# RadioSheet.net
KiCad netlist of a schematic drawn in Altium Designer
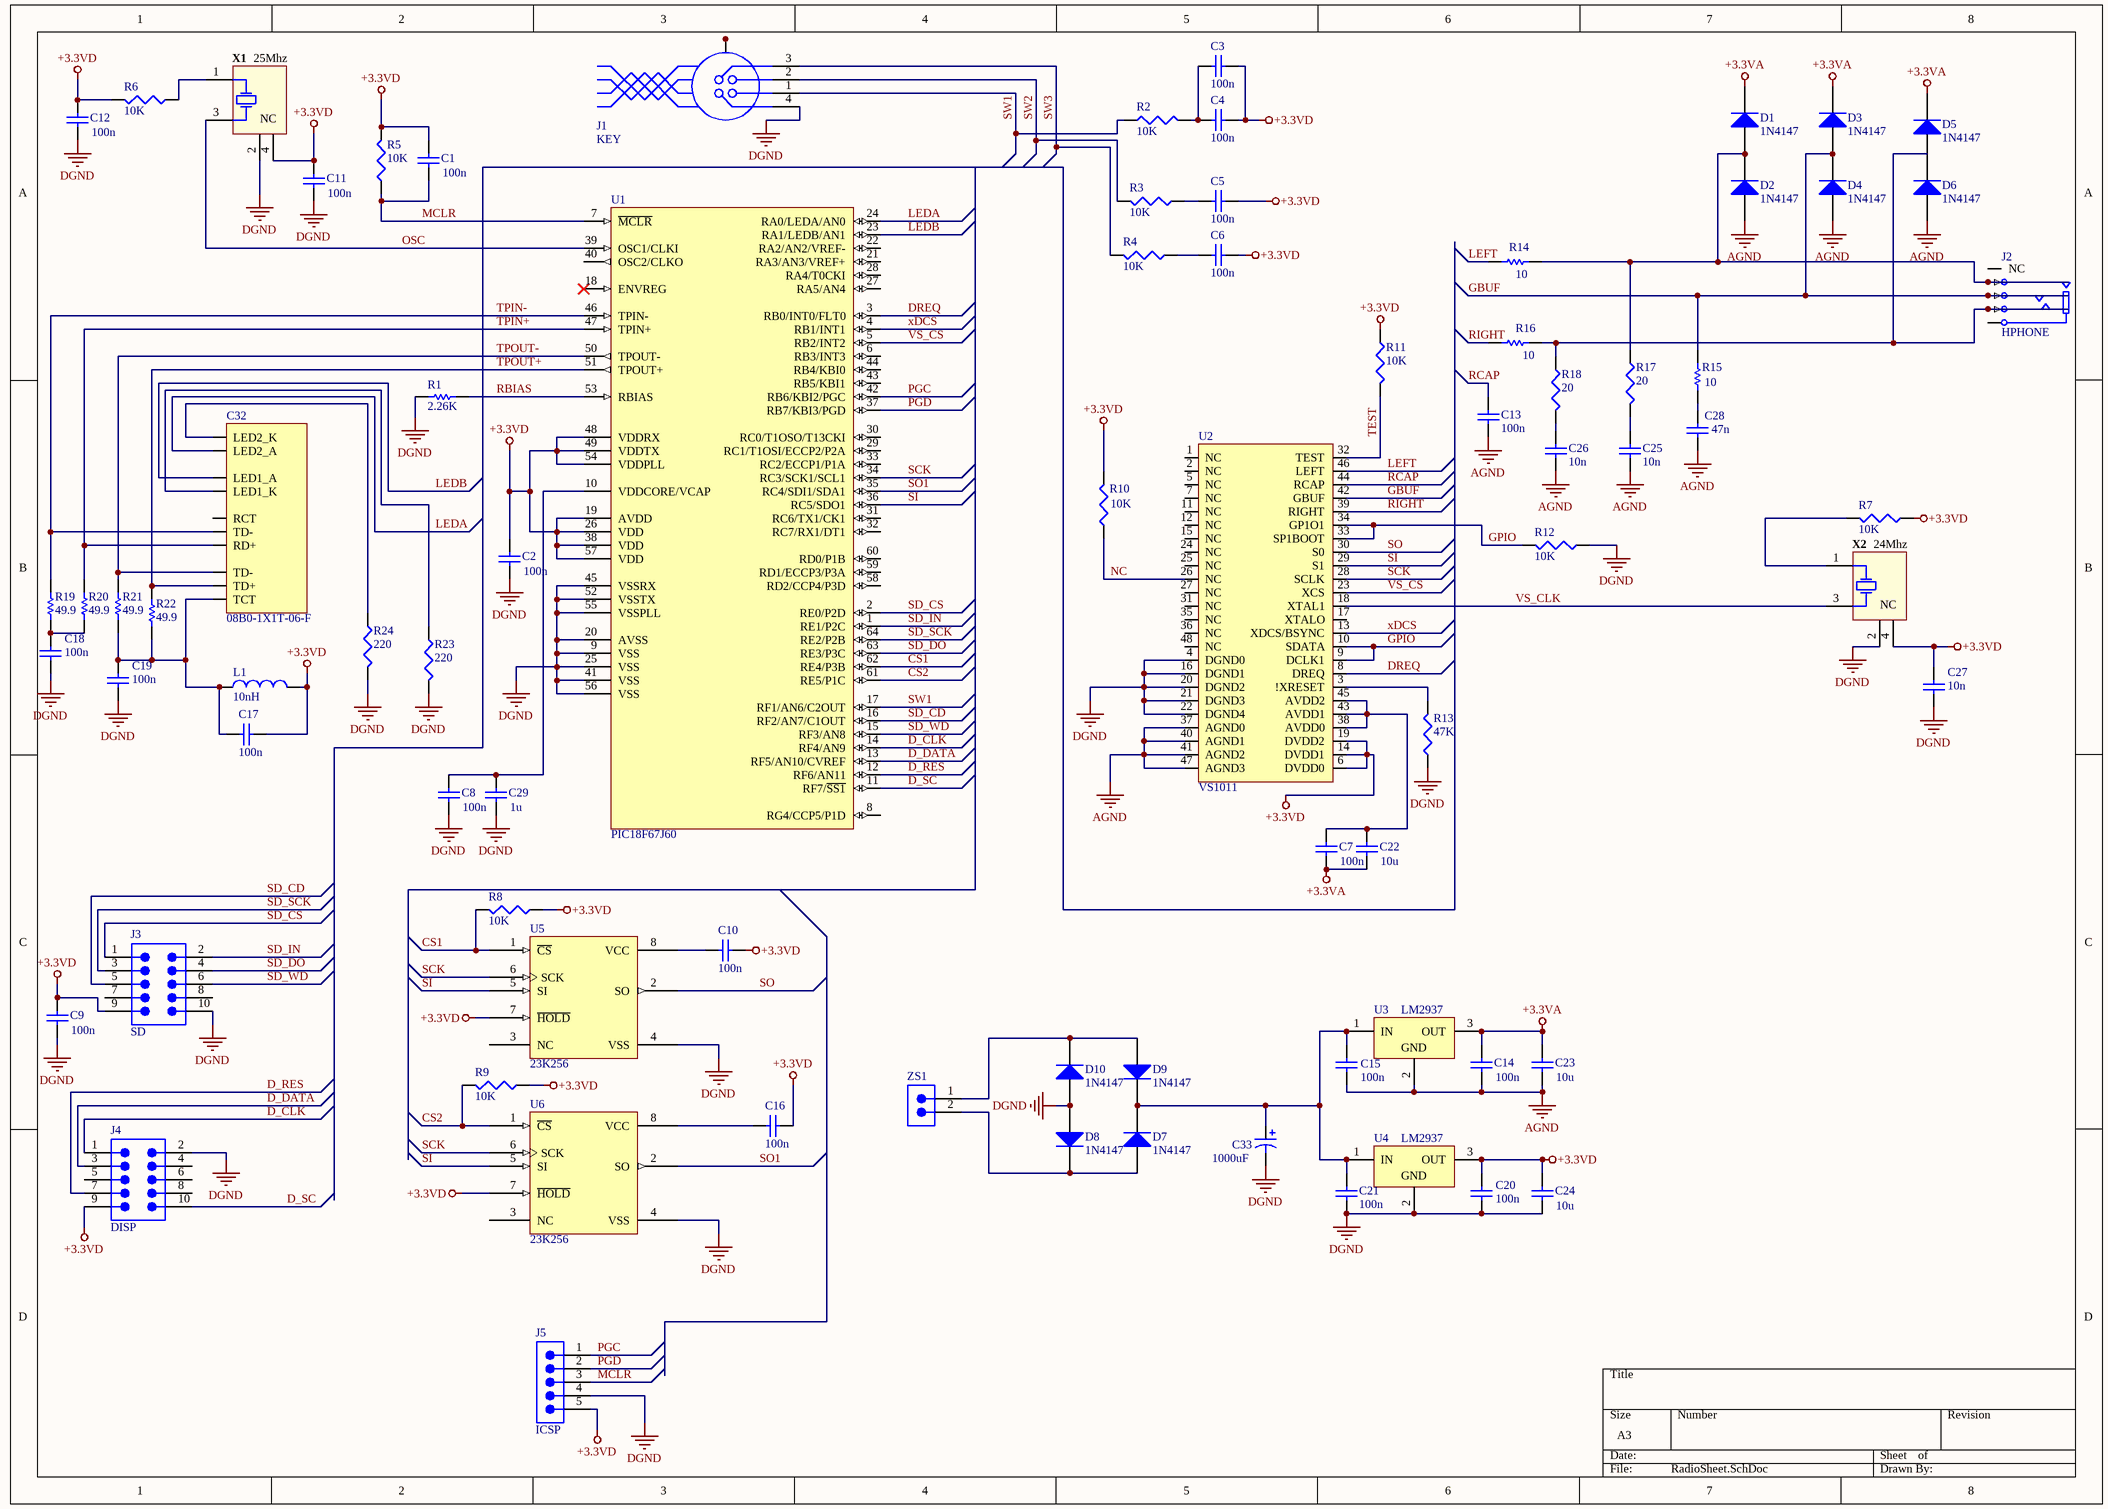
[diagram p0: RadioSheet.SchDoc]

(export (version "E")
  (design (tool "Eeschema 10.0.6"))
  (components
    (comp (ref "C1")
      (value "100n")
      (footprint "C1206")
      (description "Capacitor (Semiconductor SIM Model)")
      (fields (field (name "PUBLISHER") "Altium Limited"))
      (libsource (lib "Miscellaneous Devices") (part "Cap Semi"))
    )
    (comp (ref "C2")
      (value "100n")
      (footprint "C1206")
      (description "Capacitor (Semiconductor SIM Model)")
      (fields (field (name "PUBLISHER") "Altium Limited"))
      (libsource (lib "Miscellaneous Devices") (part "Cap Semi"))
    )
    (comp (ref "C3")
      (value "100n")
      (footprint "C1206")
      (description "Capacitor (Semiconductor SIM Model)")
      (fields (field (name "PUBLISHER") "Altium Limited"))
      (libsource (lib "Miscellaneous Devices") (part "Cap Semi"))
    )
    (comp (ref "C4")
      (value "100n")
      (footprint "C1206")
      (description "Capacitor (Semiconductor SIM Model)")
      (fields (field (name "PUBLISHER") "Altium Limited"))
      (libsource (lib "Miscellaneous Devices") (part "Cap Semi"))
    )
    (comp (ref "C5")
      (value "100n")
      (footprint "C1206")
      (description "Capacitor (Semiconductor SIM Model)")
      (fields (field (name "PUBLISHER") "Altium Limited"))
      (libsource (lib "Miscellaneous Devices") (part "Cap Semi"))
    )
    (comp (ref "C6")
      (value "100n")
      (footprint "C1206")
      (description "Capacitor (Semiconductor SIM Model)")
      (fields (field (name "PUBLISHER") "Altium Limited"))
      (libsource (lib "Miscellaneous Devices") (part "Cap Semi"))
    )
    (comp (ref "C7")
      (value "100n")
      (footprint "C1206")
      (description "Capacitor (Semiconductor SIM Model)")
      (fields (field (name "PUBLISHER") "Altium Limited"))
      (libsource (lib "Miscellaneous Devices") (part "Cap Semi"))
    )
    (comp (ref "C8")
      (value "100n")
      (footprint "C1206")
      (description "Capacitor (Semiconductor SIM Model)")
      (fields (field (name "PUBLISHER") "Altium Limited"))
      (libsource (lib "Miscellaneous Devices") (part "Cap Semi"))
    )
    (comp (ref "C9")
      (value "100n")
      (footprint "C1206")
      (description "Capacitor (Semiconductor SIM Model)")
      (fields (field (name "PUBLISHER") "Altium Limited"))
      (libsource (lib "Miscellaneous Devices") (part "Cap Semi"))
    )
    (comp (ref "C10")
      (value "100n")
      (footprint "C1206")
      (description "Capacitor (Semiconductor SIM Model)")
      (fields (field (name "PUBLISHER") "Altium Limited"))
      (libsource (lib "Miscellaneous Devices") (part "Cap Semi"))
    )
    (comp (ref "C11")
      (value "100n")
      (footprint "C1206")
      (description "Capacitor (Semiconductor SIM Model)")
      (fields (field (name "PUBLISHER") "Altium Limited"))
      (libsource (lib "Miscellaneous Devices") (part "Cap Semi"))
    )
    (comp (ref "C12")
      (value "100n")
      (footprint "C1206")
      (description "Capacitor (Semiconductor SIM Model)")
      (fields (field (name "PUBLISHER") "Altium Limited"))
      (libsource (lib "Miscellaneous Devices") (part "Cap Semi"))
    )
    (comp (ref "C13")
      (value "100n")
      (footprint "C1206")
      (description "Capacitor (Semiconductor SIM Model)")
      (fields (field (name "PUBLISHER") "Altium Limited"))
      (libsource (lib "Miscellaneous Devices") (part "Cap Semi"))
    )
    (comp (ref "C14")
      (value "100n")
      (footprint "C1206")
      (description "Capacitor (Semiconductor SIM Model)")
      (fields (field (name "PUBLISHER") "Altium Limited"))
      (libsource (lib "Miscellaneous Devices") (part "Cap Semi"))
    )
    (comp (ref "C15")
      (value "100n")
      (footprint "C1206")
      (description "Capacitor (Semiconductor SIM Model)")
      (fields (field (name "PUBLISHER") "Altium Limited"))
      (libsource (lib "Miscellaneous Devices") (part "Cap Semi"))
    )
    (comp (ref "C16")
      (value "100n")
      (footprint "C1206")
      (description "Capacitor (Semiconductor SIM Model)")
      (fields (field (name "PUBLISHER") "Altium Limited"))
      (libsource (lib "Miscellaneous Devices") (part "Cap Semi"))
    )
    (comp (ref "C17")
      (value "100n")
      (footprint "C1206")
      (description "Capacitor (Semiconductor SIM Model)")
      (fields (field (name "PUBLISHER") "Altium Limited"))
      (libsource (lib "Miscellaneous Devices") (part "Cap Semi"))
    )
    (comp (ref "C18")
      (value "100n")
      (footprint "C1206")
      (description "Capacitor (Semiconductor SIM Model)")
      (fields (field (name "PUBLISHER") "Altium Limited"))
      (libsource (lib "Miscellaneous Devices") (part "Cap Semi"))
    )
    (comp (ref "C19")
      (value "100n")
      (footprint "C1206")
      (description "Capacitor (Semiconductor SIM Model)")
      (fields (field (name "PUBLISHER") "Altium Limited"))
      (libsource (lib "Miscellaneous Devices") (part "Cap Semi"))
    )
    (comp (ref "C20")
      (value "100n")
      (footprint "C1206")
      (description "Capacitor (Semiconductor SIM Model)")
      (fields (field (name "PUBLISHER") "Altium Limited"))
      (libsource (lib "Miscellaneous Devices") (part "Cap Semi"))
    )
    (comp (ref "C21")
      (value "100n")
      (footprint "C1206")
      (description "Capacitor (Semiconductor SIM Model)")
      (fields (field (name "PUBLISHER") "Altium Limited"))
      (libsource (lib "Miscellaneous Devices") (part "Cap Semi"))
    )
    (comp (ref "C22")
      (value "10u")
      (footprint "C1206")
      (description "Capacitor (Semiconductor SIM Model)")
      (fields (field (name "PUBLISHER") "Altium Limited"))
      (libsource (lib "Miscellaneous Devices") (part "Cap Semi"))
    )
    (comp (ref "C23")
      (value "10u")
      (footprint "C1206")
      (description "Capacitor (Semiconductor SIM Model)")
      (fields (field (name "PUBLISHER") "Altium Limited"))
      (libsource (lib "") (part "Cap Semi_1"))
    )
    (comp (ref "C24")
      (value "10u")
      (footprint "C1206")
      (description "Capacitor (Semiconductor SIM Model)")
      (fields (field (name "PUBLISHER") "Altium Limited"))
      (libsource (lib "Miscellaneous Devices") (part "Cap Semi"))
    )
    (comp (ref "C25")
      (value "10n")
      (footprint "C1206")
      (description "Capacitor (Semiconductor SIM Model)")
      (fields (field (name "PUBLISHER") "Altium Limited"))
      (libsource (lib "Miscellaneous Devices") (part "Cap Semi"))
    )
    (comp (ref "C26")
      (value "10n")
      (footprint "C1206")
      (description "Capacitor (Semiconductor SIM Model)")
      (fields (field (name "PUBLISHER") "Altium Limited"))
      (libsource (lib "Miscellaneous Devices") (part "Cap Semi"))
    )
    (comp (ref "C27")
      (value "10n")
      (footprint "C1206")
      (description "Capacitor (Semiconductor SIM Model)")
      (fields (field (name "PUBLISHER") "Altium Limited"))
      (libsource (lib "Miscellaneous Devices") (part "Cap Semi"))
    )
    (comp (ref "C28")
      (value "47n")
      (footprint "C1206")
      (description "Capacitor (Semiconductor SIM Model)")
      (fields (field (name "PUBLISHER") "Altium Limited"))
      (libsource (lib "Miscellaneous Devices") (part "Cap Semi"))
    )
    (comp (ref "C29")
      (value "1u")
      (footprint "C1206")
      (description "Capacitor (Semiconductor SIM Model)")
      (fields (field (name "PUBLISHER") "Altium Limited"))
      (libsource (lib "") (part "Cap Semi_2"))
    )
    (comp (ref "C32")
      (value "08B0-1X1T-06-F")
      (footprint "RJ45")
      (libsource (lib "pads16zl") (part "08B0-1X1T-06-F"))
    )
    (comp (ref "C33")
      (value "1000uF")
      (footprint "RB7.6-15")
      (description "Polarized Capacitor (Radial)")
      (fields (field (name "Comment") "Cap Pol1") (field (name "PUBLISHER") "Altium Limited"))
      (libsource (lib "Miscellaneous Devices") (part "Cap Pol1"))
    )
    (comp (ref "D1")
      (value "1N4147")
      (footprint "GRZZ0002ZB-A")
      (description "Silicon Epitaxial Planar Diode for Various Detector, Modulator, Demodulator")
      (fields (field (name "PUBLISHER") "Altium Limited"))
      (libsource (lib "Renesas Diode") (part "1N4148"))
    )
    (comp (ref "D2")
      (value "1N4147")
      (footprint "GRZZ0002ZB-A")
      (description "Silicon Epitaxial Planar Diode for Various Detector, Modulator, Demodulator")
      (fields (field (name "PUBLISHER") "Altium Limited"))
      (libsource (lib "Renesas Diode") (part "1N4148"))
    )
    (comp (ref "D3")
      (value "1N4147")
      (footprint "GRZZ0002ZB-A")
      (description "Silicon Epitaxial Planar Diode for Various Detector, Modulator, Demodulator")
      (fields (field (name "PUBLISHER") "Altium Limited"))
      (libsource (lib "Renesas Diode") (part "1N4148"))
    )
    (comp (ref "D4")
      (value "1N4147")
      (footprint "GRZZ0002ZB-A")
      (description "Silicon Epitaxial Planar Diode for Various Detector, Modulator, Demodulator")
      (fields (field (name "PUBLISHER") "Altium Limited"))
      (libsource (lib "Renesas Diode") (part "1N4148"))
    )
    (comp (ref "D5")
      (value "1N4147")
      (footprint "GRZZ0002ZB-A")
      (description "Silicon Epitaxial Planar Diode for Various Detector, Modulator, Demodulator")
      (fields (field (name "PUBLISHER") "Altium Limited"))
      (libsource (lib "Renesas Diode") (part "1N4148"))
    )
    (comp (ref "D6")
      (value "1N4147")
      (footprint "GRZZ0002ZB-A")
      (description "Silicon Epitaxial Planar Diode for Various Detector, Modulator, Demodulator")
      (fields (field (name "PUBLISHER") "Altium Limited"))
      (libsource (lib "Renesas Diode") (part "1N4148"))
    )
    (comp (ref "D7")
      (value "1N4147")
      (footprint "GRZZ0002ZB-A")
      (description "Silicon Epitaxial Planar Diode for Various Detector, Modulator, Demodulator")
      (fields (field (name "PUBLISHER") "Altium Limited"))
      (libsource (lib "Renesas Diode") (part "1N4148"))
    )
    (comp (ref "D8")
      (value "1N4147")
      (footprint "GRZZ0002ZB-A")
      (description "Silicon Epitaxial Planar Diode for Various Detector, Modulator, Demodulator")
      (fields (field (name "PUBLISHER") "Altium Limited"))
      (libsource (lib "Renesas Diode") (part "1N4148"))
    )
    (comp (ref "D9")
      (value "1N4147")
      (footprint "GRZZ0002ZB-A")
      (description "Silicon Epitaxial Planar Diode for Various Detector, Modulator, Demodulator")
      (fields (field (name "PUBLISHER") "Altium Limited"))
      (libsource (lib "Renesas Diode") (part "1N4148"))
    )
    (comp (ref "D10")
      (value "1N4147")
      (footprint "GRZZ0002ZB-A")
      (description "Silicon Epitaxial Planar Diode for Various Detector, Modulator, Demodulator")
      (fields (field (name "PUBLISHER") "Altium Limited"))
      (libsource (lib "Renesas Diode") (part "1N4148"))
    )
    (comp (ref "J1")
      (value "KEY")
      (footprint "EPC.0B.304.HLNS")
      (fields (field (name "MANUFACTURER") "LEMO") (field (name "PARTNUMBER") "EPC.0B.304.HLNS"))
      (libsource (lib "Altium Content Vault") (part "CMP-1505-00274-1"))
    )
    (comp (ref "J2")
      (value "HPHONE")
      (footprint "PJ-386D")
      (description "Phone Jack, PJ-386D Series, Right Angle, SM, 4-Conductor Open Circuit")
      (fields (field (name "PUBLISHER") "Altium Limited"))
      (libsource (lib "Contact Technology Phone Jack") (part "TSH-3864D"))
    )
    (comp (ref "J3")
      (value "SD")
      (footprint "SMTC-TW-05-07-X-D-500-SM")
      (description "SMT Board Stacker, Vertical, -55 to 125 degC, 2 mm Pitch, 10-Pin, Male, RoHS")
      (fields (field (name "PARTNUMBER") "TW-05-07-F-D-500-SM") (field (name "MANUFACTURER") "Samtec"))
      (libsource (lib "Altium Content Vault") (part "SMTC-TW-05-07-X-D-SM"))
    )
    (comp (ref "J4")
      (value "DISP")
      (footprint "SMTC-TW-05-07-X-D-500-SM")
      (description "SMT Board Stacker, Vertical, -55 to 125 degC, 2 mm Pitch, 10-Pin, Male, RoHS")
      (fields (field (name "PARTNUMBER") "TW-05-07-F-D-500-SM") (field (name "MANUFACTURER") "Samtec"))
      (libsource (lib "Altium Content Vault") (part "CMP-1029-00393-1"))
    )
    (comp (ref "J5")
      (value "ICSP")
      (footprint "SMTC-TW-05-09-X-S-260-100")
      (description "Through-Hole Board Stacker, Vertical, -55 to 125 degC, 2 mm Pitch, 5-Pin, Male, RoHS")
      (fields (field (name "PARTNUMBER") "TW-05-09-F-S-260-100") (field (name "MANUFACTURER") "Samtec"))
      (libsource (lib "Altium Content Vault") (part "SMTC-TW-05-09-X-S-260-100"))
    )
    (comp (ref "L1")
      (value "10nH")
      (footprint "COIL-RFB1010-2_V")
      (description "Power Inductor, 56 uH +/- 10%, 2.6 A, -40 to 125 degC, 2-Pin Radial Leaded, Dia 11 mm, RoHS, Tray")
      (fields (field (name "TOLERANCE") "10%") (field (name "MANUFACTURER") "Coilcraft"))
      (libsource (lib "Altium Content Vault") (part "CMP-0899-00020-1"))
    )
    (comp (ref "R1")
      (value "2.26K")
      (footprint "AXIAL-0.3")
      (description "Resistor")
      (fields (field (name "PUBLISHER") "Altium Limited"))
      (libsource (lib "Miscellaneous Devices") (part "Res1"))
    )
    (comp (ref "R2")
      (value "10K")
      (footprint "J1-0603")
      (description "Resistor")
      (fields (field (name "PUBLISHER") "Altium Limited"))
      (libsource (lib "Miscellaneous Devices") (part "Res3"))
    )
    (comp (ref "R3")
      (value "10K")
      (footprint "J1-0603")
      (description "Resistor")
      (fields (field (name "PUBLISHER") "Altium Limited"))
      (libsource (lib "Miscellaneous Devices") (part "Res3"))
    )
    (comp (ref "R4")
      (value "10K")
      (footprint "J1-0603")
      (description "Resistor")
      (fields (field (name "PUBLISHER") "Altium Limited"))
      (libsource (lib "Miscellaneous Devices") (part "Res3"))
    )
    (comp (ref "R5")
      (value "10K")
      (footprint "J1-0603")
      (description "Resistor")
      (fields (field (name "PUBLISHER") "Altium Limited"))
      (libsource (lib "Miscellaneous Devices") (part "Res3"))
    )
    (comp (ref "R6")
      (value "10K")
      (footprint "J1-0603")
      (description "Resistor")
      (fields (field (name "PUBLISHER") "Altium Limited"))
      (libsource (lib "Miscellaneous Devices") (part "Res3"))
    )
    (comp (ref "R7")
      (value "10K")
      (footprint "J1-0603")
      (description "Resistor")
      (fields (field (name "Comment") "R5") (field (name "PUBLISHER") "Altium Limited"))
      (libsource (lib "Miscellaneous Devices") (part "Res3"))
    )
    (comp (ref "R8")
      (value "10K")
      (footprint "J1-0603")
      (description "Resistor")
      (fields (field (name "PUBLISHER") "Altium Limited"))
      (libsource (lib "Miscellaneous Devices") (part "Res3"))
    )
    (comp (ref "R9")
      (value "10K")
      (footprint "J1-0603")
      (description "Resistor")
      (fields (field (name "PUBLISHER") "Altium Limited"))
      (libsource (lib "Miscellaneous Devices") (part "Res3"))
    )
    (comp (ref "R10")
      (value "10K")
      (footprint "J1-0603")
      (description "Resistor")
      (fields (field (name "PUBLISHER") "Altium Limited"))
      (libsource (lib "Miscellaneous Devices") (part "Res3"))
    )
    (comp (ref "R11")
      (value "10K")
      (footprint "J1-0603")
      (description "Resistor")
      (fields (field (name "PUBLISHER") "Altium Limited"))
      (libsource (lib "Miscellaneous Devices") (part "Res3"))
    )
    (comp (ref "R12")
      (value "10K")
      (footprint "J1-0603")
      (description "Resistor")
      (fields (field (name "PUBLISHER") "Altium Limited"))
      (libsource (lib "Miscellaneous Devices") (part "Res3"))
    )
    (comp (ref "R13")
      (value "47K")
      (footprint "J1-0603")
      (description "Resistor")
      (fields (field (name "PUBLISHER") "Altium Limited"))
      (libsource (lib "Miscellaneous Devices") (part "Res3"))
    )
    (comp (ref "R14")
      (value "10")
      (footprint "8RB-1206")
      (fields (field (name "PUBLISHER") "Altium Limited"))
      (libsource (lib "Panasonic Resistor") (part "ERJ8BQ"))
    )
    (comp (ref "R15")
      (value "10")
      (footprint "8RB-1206")
      (fields (field (name "PUBLISHER") "Altium Limited"))
      (libsource (lib "Panasonic Resistor") (part "ERJ8BQ"))
    )
    (comp (ref "R16")
      (value "10")
      (footprint "8RB-1206")
      (fields (field (name "PUBLISHER") "Altium Limited"))
      (libsource (lib "Panasonic Resistor") (part "ERJ8BQ"))
    )
    (comp (ref "R17")
      (value "20")
      (footprint "J1-0603")
      (description "Resistor")
      (fields (field (name "PUBLISHER") "Altium Limited"))
      (libsource (lib "Miscellaneous Devices") (part "Res3"))
    )
    (comp (ref "R18")
      (value "20")
      (footprint "J1-0603")
      (description "Resistor")
      (fields (field (name "PUBLISHER") "Altium Limited"))
      (libsource (lib "Miscellaneous Devices") (part "Res3"))
    )
    (comp (ref "R19")
      (value "49.9")
      (footprint "6-0805")
      (fields (field (name "PUBLISHER") "Altium Limited"))
      (libsource (lib "Panasonic Resistor") (part "ERJ6BQ"))
    )
    (comp (ref "R20")
      (value "49.9")
      (footprint "6-0805")
      (fields (field (name "PUBLISHER") "Altium Limited"))
      (libsource (lib "Panasonic Resistor") (part "ERJ6BQ"))
    )
    (comp (ref "R21")
      (value "49.9")
      (footprint "6-0805")
      (fields (field (name "PUBLISHER") "Altium Limited"))
      (libsource (lib "Panasonic Resistor") (part "ERJ6BQ"))
    )
    (comp (ref "R22")
      (value "49.9")
      (footprint "6-0805")
      (fields (field (name "PUBLISHER") "Altium Limited"))
      (libsource (lib "Panasonic Resistor") (part "ERJ6BQ"))
    )
    (comp (ref "R23")
      (value "220")
      (footprint "J1-0603")
      (description "Resistor")
      (fields (field (name "Comment") "R5") (field (name "PUBLISHER") "Altium Limited"))
      (libsource (lib "Miscellaneous Devices") (part "Res3"))
    )
    (comp (ref "R24")
      (value "220")
      (footprint "J1-0603")
      (description "Resistor")
      (fields (field (name "Comment") "R5") (field (name "PUBLISHER") "Altium Limited"))
      (libsource (lib "Miscellaneous Devices") (part "Res3"))
    )
    (comp (ref "U1")
      (value "PIC18F67J60")
      (footprint "TQFP-PT64_M")
      (libsource (lib "Altium Content Vault") (part "CMP-0116-00618-1"))
    )
    (comp (ref "U2") (value "VS1011") (footprint "LQFP-48") (libsource (lib "pads16zl") (part "VS1011")))
    (comp (ref "U3")
      (value "LM2937")
      (footprint "NDE0003A")
      (description "400mA and 500mA Voltage Regulator, 3-pin TO-220, Pb-Free")
      (fields (field (name "MANUFACTURER") "Texas Instruments"))
      (libsource (lib "Altium Content Vault") (part "PM-REG-LM2940-SIL3"))
    )
    (comp (ref "U4")
      (value "LM2937")
      (footprint "NDE0003A")
      (description "400mA and 500mA Voltage Regulator, 3-pin TO-220, Pb-Free")
      (fields (field (name "MANUFACTURER") "Texas Instruments"))
      (libsource (lib "Altium Content Vault") (part "PM-REG-LM2940-SIL3"))
    )
    (comp (ref "U5")
      (value "23K256")
      (footprint "TSSOP-ST8_M")
      (description "256K, 32768x8-bit, 3.6V SPI Serial SRAM, 8-Pin TSSOP, Extended TemperatureTape and Reel")
      (libsource (lib "Altium Content Vault") (part "CMP-0163-00021-1"))
    )
    (comp (ref "U6")
      (value "23K256")
      (footprint "TSSOP-ST8_M")
      (description "256K, 32768x8-bit, 3.6V SPI Serial SRAM, 8-Pin TSSOP, Extended TemperatureTape and Reel")
      (libsource (lib "Altium Content Vault") (part "CMP-0163-00021-1"))
    )
    (comp (ref "X1")
      (value "25Mhz")
      (footprint "AVX-CX3225GB-4_V")
      (description "Crystal Unit, 8 pF, 25000 kHz, -10 to 70 degC, 4-Pin 3.2 x 2.5 x 0.8 mm SMD, RoHS, Tape and Reel")
      (fields (field (name "MANUFACTURER") "Kyocera") (field (name "PARTNUMBER") "CX3225GB25000D0HEQCC"))
      (libsource (lib "Altium Content Vault") (part "AVX-CX3225GB-XTAL-4"))
    )
    (comp (ref "X2")
      (value "24Mhz")
      (footprint "AVX-CX3225GB-4_V")
      (description "Crystal Unit, 8 pF, 25000 kHz, -10 to 70 degC, 4-Pin 3.2 x 2.5 x 0.8 mm SMD, RoHS, Tape and Reel")
      (fields (field (name "MANUFACTURER") "Kyocera") (field (name "PARTNUMBER") "CX3225GB25000D0HEQCC"))
      (libsource (lib "Altium Content Vault") (part "AVX-CX3225GB-XTAL-4"))
    )
    (comp (ref "ZS1")
      (value "~")
      (footprint "SMTC-TSW-102-08-X-S-RA")
      (fields (field (name "MANUFACTURER") "Samtec") (field (name "PARTNUMBER") "TSW-102-08-G-S-RA"))
      (libsource (lib "Altium Content Vault") (part "SMTC-TSW-102-X-X-S-X"))
    )
  )
  (nets
    (net (code "1") (name "+3.3VA") (class "Default")
      (node (ref "C14") (pin "2") (pinfunction "2_2") (pintype "passive"))
      (node (ref "C22") (pin "1") (pinfunction "1_1") (pintype "passive"))
      (node (ref "C23") (pin "1") (pinfunction "1_1") (pintype "passive"))
      (node (ref "C7") (pin "1") (pinfunction "1_1") (pintype "passive"))
      (node (ref "D1") (pin "1") (pinfunction "K_1") (pintype "passive"))
      (node (ref "D3") (pin "1") (pinfunction "K_1") (pintype "passive"))
      (node (ref "D5") (pin "1") (pinfunction "K_1") (pintype "passive"))
      (node (ref "U3") (pin "3") (pinfunction "OUT_3") (pintype "power_in"))
    )
    (net (code "2") (name "+3.3VD") (class "Default")
      (node (ref "C1") (pin "2") (pinfunction "2_2") (pintype "passive"))
      (node (ref "C10") (pin "1") (pinfunction "1_1") (pintype "passive"))
      (node (ref "C11") (pin "2") (pinfunction "2_2") (pintype "passive"))
      (node (ref "C12") (pin "2") (pinfunction "2_2") (pintype "passive"))
      (node (ref "C16") (pin "1") (pinfunction "1_1") (pintype "passive"))
      (node (ref "C17") (pin "1") (pinfunction "1_1") (pintype "passive"))
      (node (ref "C2") (pin "2") (pinfunction "2_2") (pintype "passive"))
      (node (ref "C20") (pin "2") (pinfunction "2_2") (pintype "passive"))
      (node (ref "C24") (pin "2") (pinfunction "2_2") (pintype "passive"))
      (node (ref "C27") (pin "2") (pinfunction "2_2") (pintype "passive"))
      (node (ref "C3") (pin "1") (pinfunction "1_1") (pintype "passive"))
      (node (ref "C4") (pin "2") (pinfunction "2_2") (pintype "passive"))
      (node (ref "C5") (pin "1") (pinfunction "1_1") (pintype "passive"))
      (node (ref "C6") (pin "1") (pinfunction "1_1") (pintype "passive"))
      (node (ref "C9") (pin "2") (pinfunction "2_2") (pintype "passive"))
      (node (ref "J3") (pin "9") (pinfunction "9_9") (pintype "passive"))
      (node (ref "J4") (pin "9") (pinfunction "9_9") (pintype "passive"))
      (node (ref "J5") (pin "5") (pinfunction "5_5") (pintype "passive"))
      (node (ref "L1") (pin "2") (pinfunction "2_2") (pintype "passive"))
      (node (ref "R10") (pin "2") (pinfunction "2_2") (pintype "passive"))
      (node (ref "R11") (pin "1") (pinfunction "1_1") (pintype "passive"))
      (node (ref "R5") (pin "2") (pinfunction "2_2") (pintype "passive"))
      (node (ref "R6") (pin "2") (pinfunction "2_2") (pintype "passive"))
      (node (ref "R7") (pin "1") (pinfunction "1_1") (pintype "passive"))
      (node (ref "R8") (pin "1") (pinfunction "1_1") (pintype "passive"))
      (node (ref "R9") (pin "1") (pinfunction "1_1") (pintype "passive"))
      (node (ref "U1") (pin "19") (pinfunction "AVDD_19") (pintype "power_in"))
      (node (ref "U1") (pin "26") (pinfunction "VDD_26") (pintype "power_in"))
      (node (ref "U1") (pin "38") (pinfunction "VDD_38") (pintype "power_in"))
      (node (ref "U1") (pin "48") (pinfunction "VDDRX_48") (pintype "power_in"))
      (node (ref "U1") (pin "49") (pinfunction "VDDTX_49") (pintype "power_in"))
      (node (ref "U1") (pin "54") (pinfunction "VDDPLL_54") (pintype "power_in"))
      (node (ref "U1") (pin "57") (pinfunction "VDD_57") (pintype "power_in"))
      (node (ref "U2") (pin "14") (pinfunction "DVDD1_14") (pintype "passive"))
      (node (ref "U2") (pin "19") (pinfunction "DVDD2_19") (pintype "passive"))
      (node (ref "U2") (pin "6") (pinfunction "DVDD0_6") (pintype "passive"))
      (node (ref "U4") (pin "3") (pinfunction "OUT_3") (pintype "power_in"))
      (node (ref "U5") (pin "7") (pinfunction "~{HOLD}_7") (pintype "input"))
      (node (ref "U6") (pin "7") (pinfunction "~{HOLD}_7") (pintype "input"))
      (node (ref "X1") (pin "4") (pinfunction "NC_4") (pintype "passive"))
      (node (ref "X2") (pin "4") (pinfunction "NC_4") (pintype "passive"))
    )
    (net (code "3") (name "/CS1") (class "Default")
      (node (ref "R8") (pin "2") (pinfunction "2_2") (pintype "passive"))
      (node (ref "U1") (pin "62") (pinfunction "RE4/P3B_62") (pintype "bidirectional"))
      (node (ref "U5") (pin "1") (pinfunction "~{CS}_1") (pintype "input"))
    )
    (net (code "4") (name "/CS2") (class "Default")
      (node (ref "R9") (pin "2") (pinfunction "2_2") (pintype "passive"))
      (node (ref "U1") (pin "61") (pinfunction "RE5/P1C_61") (pintype "bidirectional"))
      (node (ref "U6") (pin "1") (pinfunction "~{CS}_1") (pintype "input"))
    )
    (net (code "5") (name "/DREQ") (class "Default")
      (node (ref "U1") (pin "3") (pinfunction "RB0/INT0/FLT0_3") (pintype "bidirectional"))
      (node (ref "U2") (pin "8") (pinfunction "DREQ_8") (pintype "passive"))
    )
    (net (code "6") (name "/D_CLK") (class "Default")
      (node (ref "J4") (pin "1") (pinfunction "1_1") (pintype "passive"))
      (node (ref "U1") (pin "14") (pinfunction "RF4/AN9_14") (pintype "bidirectional"))
    )
    (net (code "7") (name "/D_DATA") (class "Default")
      (node (ref "J4") (pin "3") (pinfunction "3_3") (pintype "passive"))
      (node (ref "U1") (pin "13") (pinfunction "RF5/AN10/CVREF_13") (pintype "bidirectional"))
    )
    (net (code "8") (name "/D_RES") (class "Default")
      (node (ref "J4") (pin "7") (pinfunction "7_7") (pintype "passive"))
      (node (ref "U1") (pin "12") (pinfunction "RF6/AN11_12") (pintype "bidirectional"))
    )
    (net (code "9") (name "/D_SC") (class "Default")
      (node (ref "J4") (pin "10") (pinfunction "10_10") (pintype "passive"))
      (node (ref "U1") (pin "11") (pinfunction "RF7/~{SS1}_11") (pintype "bidirectional"))
    )
    (net (code "10") (name "/GBUF") (class "Default")
      (node (ref "D3") (pin "2") (pinfunction "A_2") (pintype "passive"))
      (node (ref "D4") (pin "1") (pinfunction "K_1") (pintype "passive"))
      (node (ref "J2") (pin "2") (pinfunction "T_2") (pintype "input"))
      (node (ref "R15") (pin "2") (pinfunction "2_2") (pintype "passive"))
      (node (ref "U2") (pin "42") (pinfunction "GBUF_42") (pintype "passive"))
    )
    (net (code "11") (name "/GPIO") (class "Default")
      (node (ref "R12") (pin "2") (pinfunction "2_2") (pintype "passive"))
      (node (ref "U2") (pin "10") (pinfunction "SDATA_10") (pintype "passive"))
      (node (ref "U2") (pin "33") (pinfunction "SP1BOOT_33") (pintype "passive"))
      (node (ref "U2") (pin "34") (pinfunction "GP1O1_34") (pintype "passive"))
      (node (ref "U2") (pin "9") (pinfunction "DCLK1_9") (pintype "passive"))
    )
    (net (code "12") (name "/LEDA") (class "Default")
      (node (ref "C32") (pin "9") (pinfunction "LED2_A_9") (pintype "passive"))
      (node (ref "U1") (pin "24") (pinfunction "RA0/LEDA/AN0_24") (pintype "bidirectional"))
    )
    (net (code "13") (name "/LEDB") (class "Default")
      (node (ref "C32") (pin "8") (pinfunction "LED1_A_8") (pintype "passive"))
      (node (ref "U1") (pin "23") (pinfunction "RA1/LEDB/AN1_23") (pintype "bidirectional"))
    )
    (net (code "14") (name "/LEFT") (class "Default")
      (node (ref "R14") (pin "2") (pinfunction "2_2") (pintype "passive"))
      (node (ref "U2") (pin "46") (pinfunction "LEFT_46") (pintype "passive"))
    )
    (net (code "15") (name "/MCLR") (class "Default")
      (node (ref "C1") (pin "1") (pinfunction "1_1") (pintype "passive"))
      (node (ref "J5") (pin "3") (pinfunction "3_3") (pintype "passive"))
      (node (ref "R5") (pin "1") (pinfunction "1_1") (pintype "passive"))
      (node (ref "U1") (pin "7") (pinfunction "~{MCLR}_7") (pintype "input"))
    )
    (net (code "16") (name "/NC") (class "Default")
      (node (ref "R10") (pin "1") (pinfunction "1_1") (pintype "passive"))
      (node (ref "U2") (pin "26") (pinfunction "NC_26") (pintype "passive"))
    )
    (net (code "17") (name "/OSC") (class "Default")
      (node (ref "U1") (pin "39") (pinfunction "OSC1/CLKI_39") (pintype "input"))
      (node (ref "X1") (pin "3") (pinfunction "HOT_3") (pintype "passive"))
    )
    (net (code "18") (name "/PGC") (class "Default")
      (node (ref "J5") (pin "1") (pinfunction "1_1") (pintype "passive"))
      (node (ref "U1") (pin "42") (pinfunction "RB6/KBI2/PGC_42") (pintype "bidirectional"))
    )
    (net (code "19") (name "/PGD") (class "Default")
      (node (ref "J5") (pin "2") (pinfunction "2_2") (pintype "passive"))
      (node (ref "U1") (pin "37") (pinfunction "RB7/KBI3/PGD_37") (pintype "bidirectional"))
    )
    (net (code "20") (name "/RBIAS") (class "Default")
      (node (ref "R1") (pin "2") (pinfunction "2_2") (pintype "passive"))
      (node (ref "U1") (pin "53") (pinfunction "RBIAS_53") (pintype "input"))
    )
    (net (code "21") (name "/RCAP") (class "Default")
      (node (ref "C13") (pin "2") (pinfunction "2_2") (pintype "passive"))
      (node (ref "U2") (pin "44") (pinfunction "RCAP_44") (pintype "passive"))
    )
    (net (code "22") (name "/RIGHT") (class "Default")
      (node (ref "R16") (pin "2") (pinfunction "2_2") (pintype "passive"))
      (node (ref "U2") (pin "39") (pinfunction "RIGHT_39") (pintype "passive"))
    )
    (net (code "23") (name "/SCK") (class "Default")
      (node (ref "U1") (pin "34") (pinfunction "RC3/SCK1/SCL1_34") (pintype "bidirectional"))
      (node (ref "U2") (pin "28") (pinfunction "SCLK_28") (pintype "passive"))
      (node (ref "U5") (pin "6") (pinfunction "SCK_6") (pintype "input"))
      (node (ref "U6") (pin "6") (pinfunction "SCK_6") (pintype "input"))
    )
    (net (code "24") (name "/SD_CD") (class "Default")
      (node (ref "J3") (pin "5") (pinfunction "5_5") (pintype "passive"))
      (node (ref "U1") (pin "16") (pinfunction "RF2/AN7/C1OUT_16") (pintype "bidirectional"))
    )
    (net (code "25") (name "/SD_CS") (class "Default")
      (node (ref "J3") (pin "1") (pinfunction "1_1") (pintype "passive"))
      (node (ref "U1") (pin "2") (pinfunction "RE0/P2D_2") (pintype "bidirectional"))
    )
    (net (code "26") (name "/SD_DO") (class "Default")
      (node (ref "J3") (pin "4") (pinfunction "4_4") (pintype "passive"))
      (node (ref "U1") (pin "63") (pinfunction "RE3/P3C_63") (pintype "bidirectional"))
    )
    (net (code "27") (name "/SD_IN") (class "Default")
      (node (ref "J3") (pin "2") (pinfunction "2_2") (pintype "passive"))
      (node (ref "U1") (pin "1") (pinfunction "RE1/P2C_1") (pintype "bidirectional"))
    )
    (net (code "28") (name "/SD_SCK") (class "Default")
      (node (ref "J3") (pin "3") (pinfunction "3_3") (pintype "passive"))
      (node (ref "U1") (pin "64") (pinfunction "RE2/P2B_64") (pintype "bidirectional"))
    )
    (net (code "29") (name "/SD_WD") (class "Default")
      (node (ref "J3") (pin "6") (pinfunction "6_6") (pintype "passive"))
      (node (ref "U1") (pin "15") (pinfunction "RF3/AN8_15") (pintype "bidirectional"))
    )
    (net (code "30") (name "/SI") (class "Default")
      (node (ref "U1") (pin "36") (pinfunction "RC5/SDO1_36") (pintype "bidirectional"))
      (node (ref "U2") (pin "29") (pinfunction "S1_29") (pintype "passive"))
      (node (ref "U5") (pin "5") (pinfunction "SI_5") (pintype "input"))
      (node (ref "U6") (pin "5") (pinfunction "SI_5") (pintype "input"))
    )
    (net (code "31") (name "/SO") (class "Default")
      (node (ref "U2") (pin "30") (pinfunction "S0_30") (pintype "passive"))
      (node (ref "U5") (pin "2") (pinfunction "SO_2") (pintype "output"))
    )
    (net (code "32") (name "/SO1") (class "Default")
      (node (ref "U1") (pin "35") (pinfunction "RC4/SDI1/SDA1_35") (pintype "bidirectional"))
      (node (ref "U6") (pin "2") (pinfunction "SO_2") (pintype "output"))
    )
    (net (code "33") (name "/SW1") (class "Default")
      (node (ref "J1") (pin "1") (pinfunction "1_1") (pintype "passive"))
      (node (ref "R2") (pin "1") (pinfunction "1_1") (pintype "passive"))
      (node (ref "U1") (pin "17") (pinfunction "RF1/AN6/C2OUT_17") (pintype "bidirectional"))
    )
    (net (code "34") (name "/SW2") (class "Default")
      (node (ref "J1") (pin "2") (pinfunction "2_2") (pintype "passive"))
      (node (ref "R3") (pin "2") (pinfunction "2_2") (pintype "passive"))
    )
    (net (code "35") (name "/SW3") (class "Default")
      (node (ref "J1") (pin "3") (pinfunction "3_3") (pintype "passive"))
      (node (ref "R4") (pin "2") (pinfunction "2_2") (pintype "passive"))
    )
    (net (code "36") (name "/TEST") (class "Default")
      (node (ref "R11") (pin "2") (pinfunction "2_2") (pintype "passive"))
      (node (ref "U2") (pin "32") (pinfunction "TEST_32") (pintype "passive"))
    )
    (net (code "37") (name "/TPIN+") (class "Default")
      (node (ref "C32") (pin "4") (pinfunction "RD+_4") (pintype "passive"))
      (node (ref "R20") (pin "2") (pinfunction "2_2") (pintype "passive"))
      (node (ref "U1") (pin "47") (pinfunction "TPIN+_47") (pintype "input"))
    )
    (net (code "38") (name "/TPIN-") (class "Default")
      (node (ref "C32") (pin "5") (pinfunction "TD-_5") (pintype "passive"))
      (node (ref "R19") (pin "2") (pinfunction "2_2") (pintype "passive"))
      (node (ref "U1") (pin "46") (pinfunction "TPIN-_46") (pintype "input"))
    )
    (net (code "39") (name "/TPOUT+") (class "Default")
      (node (ref "C32") (pin "2") (pinfunction "TD+_2") (pintype "passive"))
      (node (ref "R22") (pin "2") (pinfunction "2_2") (pintype "passive"))
      (node (ref "U1") (pin "51") (pinfunction "TPOUT+_51") (pintype "output"))
    )
    (net (code "40") (name "/TPOUT-") (class "Default")
      (node (ref "C32") (pin "3") (pinfunction "TD-_3") (pintype "passive"))
      (node (ref "R21") (pin "2") (pinfunction "2_2") (pintype "passive"))
      (node (ref "U1") (pin "50") (pinfunction "TPOUT-_50") (pintype "output"))
    )
    (net (code "41") (name "/VS_CLK") (class "Default")
      (node (ref "U2") (pin "18") (pinfunction "XTAL1_18") (pintype "passive"))
      (node (ref "X2") (pin "3") (pinfunction "HOT_3") (pintype "passive"))
    )
    (net (code "42") (name "/VS_CS") (class "Default")
      (node (ref "U1") (pin "5") (pinfunction "RB2/INT2_5") (pintype "bidirectional"))
      (node (ref "U2") (pin "23") (pinfunction "XCS_23") (pintype "passive"))
    )
    (net (code "43") (name "/xDCS") (class "Default")
      (node (ref "U1") (pin "4") (pinfunction "RB1/INT1_4") (pintype "bidirectional"))
      (node (ref "U2") (pin "13") (pinfunction "XDCS/BSYNC_13") (pintype "passive"))
    )
    (net (code "44") (name "AGND") (class "Default")
      (node (ref "C13") (pin "1") (pinfunction "1_1") (pintype "passive"))
      (node (ref "C14") (pin "1") (pinfunction "1_1") (pintype "passive"))
      (node (ref "C15") (pin "1") (pinfunction "1_1") (pintype "passive"))
      (node (ref "C23") (pin "2") (pinfunction "2_2") (pintype "passive"))
      (node (ref "C25") (pin "1") (pinfunction "1_1") (pintype "passive"))
      (node (ref "C26") (pin "1") (pinfunction "1_1") (pintype "passive"))
      (node (ref "C28") (pin "1") (pinfunction "1_1") (pintype "passive"))
      (node (ref "D2") (pin "2") (pinfunction "A_2") (pintype "passive"))
      (node (ref "D4") (pin "2") (pinfunction "A_2") (pintype "passive"))
      (node (ref "D6") (pin "2") (pinfunction "A_2") (pintype "passive"))
      (node (ref "U2") (pin "37") (pinfunction "AGND0_37") (pintype "passive"))
      (node (ref "U2") (pin "40") (pinfunction "AGND1_40") (pintype "passive"))
      (node (ref "U2") (pin "41") (pinfunction "AGND2_41") (pintype "passive"))
      (node (ref "U2") (pin "47") (pinfunction "AGND3_47") (pintype "passive"))
      (node (ref "U3") (pin "2") (pinfunction "GND_2") (pintype "power_in"))
    )
    (net (code "45") (name "DGND") (class "Default")
      (node (ref "C11") (pin "1") (pinfunction "1_1") (pintype "passive"))
      (node (ref "C12") (pin "1") (pinfunction "1_1") (pintype "passive"))
      (node (ref "C18") (pin "1") (pinfunction "1_1") (pintype "passive"))
      (node (ref "C19") (pin "1") (pinfunction "1_1") (pintype "passive"))
      (node (ref "C2") (pin "1") (pinfunction "1_1") (pintype "passive"))
      (node (ref "C20") (pin "1") (pinfunction "1_1") (pintype "passive"))
      (node (ref "C21") (pin "1") (pinfunction "1_1") (pintype "passive"))
      (node (ref "C24") (pin "1") (pinfunction "1_1") (pintype "passive"))
      (node (ref "C27") (pin "1") (pinfunction "1_1") (pintype "passive"))
      (node (ref "C29") (pin "1") (pinfunction "1_1") (pintype "passive"))
      (node (ref "C33") (pin "2") (pinfunction "2_2") (pintype "passive"))
      (node (ref "C8") (pin "1") (pinfunction "1_1") (pintype "passive"))
      (node (ref "C9") (pin "1") (pinfunction "1_1") (pintype "passive"))
      (node (ref "D10") (pin "2") (pinfunction "A_2") (pintype "passive"))
      (node (ref "D8") (pin "2") (pinfunction "A_2") (pintype "passive"))
      (node (ref "J1") (pin "4") (pinfunction "4_4") (pintype "passive"))
      (node (ref "J3") (pin "10") (pinfunction "10_10") (pintype "passive"))
      (node (ref "J4") (pin "2") (pinfunction "2_2") (pintype "passive"))
      (node (ref "J5") (pin "4") (pinfunction "4_4") (pintype "passive"))
      (node (ref "R1") (pin "1") (pinfunction "1_1") (pintype "passive"))
      (node (ref "R12") (pin "1") (pinfunction "1_1") (pintype "passive"))
      (node (ref "R13") (pin "1") (pinfunction "1_1") (pintype "passive"))
      (node (ref "R23") (pin "2") (pinfunction "2_2") (pintype "passive"))
      (node (ref "R24") (pin "2") (pinfunction "2_2") (pintype "passive"))
      (node (ref "U1") (pin "20") (pinfunction "AVSS_20") (pintype "power_in"))
      (node (ref "U1") (pin "25") (pinfunction "VSS_25") (pintype "power_in"))
      (node (ref "U1") (pin "41") (pinfunction "VSS_41") (pintype "power_in"))
      (node (ref "U1") (pin "45") (pinfunction "VSSRX_45") (pintype "power_in"))
      (node (ref "U1") (pin "52") (pinfunction "VSSTX_52") (pintype "power_in"))
      (node (ref "U1") (pin "55") (pinfunction "VSSPLL_55") (pintype "power_in"))
      (node (ref "U1") (pin "56") (pinfunction "VSS_56") (pintype "power_in"))
      (node (ref "U1") (pin "9") (pinfunction "VSS_9") (pintype "power_in"))
      (node (ref "U2") (pin "16") (pinfunction "DGND1_16") (pintype "passive"))
      (node (ref "U2") (pin "20") (pinfunction "DGND2_20") (pintype "passive"))
      (node (ref "U2") (pin "21") (pinfunction "DGND3_21") (pintype "passive"))
      (node (ref "U2") (pin "22") (pinfunction "DGND4_22") (pintype "passive"))
      (node (ref "U2") (pin "4") (pinfunction "DGND0_4") (pintype "passive"))
      (node (ref "U4") (pin "2") (pinfunction "GND_2") (pintype "power_in"))
      (node (ref "U5") (pin "4") (pinfunction "VSS_4") (pintype "power_in"))
      (node (ref "U6") (pin "4") (pinfunction "VSS_4") (pintype "power_in"))
      (node (ref "X1") (pin "2") (pinfunction "NC_2") (pintype "passive"))
      (node (ref "X2") (pin "2") (pinfunction "NC_2") (pintype "passive"))
    )
    (net (code "46") (name "Net-(C3-Pad2)") (class "Default")
      (node (ref "C3") (pin "2") (pinfunction "2_2") (pintype "passive"))
      (node (ref "C4") (pin "1") (pinfunction "1_1") (pintype "passive"))
      (node (ref "R2") (pin "2") (pinfunction "2_2") (pintype "passive"))
    )
    (net (code "47") (name "Net-(C5-Pad2)") (class "Default")
      (node (ref "C5") (pin "2") (pinfunction "2_2") (pintype "passive"))
      (node (ref "R3") (pin "1") (pinfunction "1_1") (pintype "passive"))
    )
    (net (code "48") (name "Net-(C6-Pad2)") (class "Default")
      (node (ref "C6") (pin "2") (pinfunction "2_2") (pintype "passive"))
      (node (ref "R4") (pin "1") (pinfunction "1_1") (pintype "passive"))
    )
    (net (code "49") (name "Net-(C18-Pad2)") (class "Default")
      (node (ref "C18") (pin "2") (pinfunction "2_2") (pintype "passive"))
      (node (ref "R19") (pin "1") (pinfunction "1_1") (pintype "passive"))
      (node (ref "R20") (pin "1") (pinfunction "1_1") (pintype "passive"))
    )
    (net (code "50") (name "Net-(C25-Pad2)") (class "Default")
      (node (ref "C25") (pin "2") (pinfunction "2_2") (pintype "passive"))
      (node (ref "R17") (pin "2") (pinfunction "2_2") (pintype "passive"))
    )
    (net (code "51") (name "Net-(C26-Pad2)") (class "Default")
      (node (ref "C26") (pin "2") (pinfunction "2_2") (pintype "passive"))
      (node (ref "R18") (pin "2") (pinfunction "2_2") (pintype "passive"))
    )
    (net (code "52") (name "Net-(C28-Pad2)") (class "Default")
      (node (ref "C28") (pin "2") (pinfunction "2_2") (pintype "passive"))
      (node (ref "R15") (pin "1") (pinfunction "1_1") (pintype "passive"))
    )
    (net (code "53") (name "Net-(C32-LED1_K)") (class "Default")
      (node (ref "C32") (pin "7") (pinfunction "LED1_K_7") (pintype "passive"))
      (node (ref "R23") (pin "1") (pinfunction "1_1") (pintype "passive"))
    )
    (net (code "54") (name "Net-(C32-LED2_K)") (class "Default")
      (node (ref "C32") (pin "10") (pinfunction "LED2_K_10") (pintype "passive"))
      (node (ref "R24") (pin "1") (pinfunction "1_1") (pintype "passive"))
    )
    (net (code "55") (name "Net-(C32-TCT)") (class "Default")
      (node (ref "C17") (pin "2") (pinfunction "2_2") (pintype "passive"))
      (node (ref "C19") (pin "2") (pinfunction "2_2") (pintype "passive"))
      (node (ref "C32") (pin "1") (pinfunction "TCT_1") (pintype "passive"))
      (node (ref "L1") (pin "1") (pinfunction "1_1") (pintype "passive"))
      (node (ref "R21") (pin "1") (pinfunction "1_1") (pintype "passive"))
      (node (ref "R22") (pin "1") (pinfunction "1_1") (pintype "passive"))
    )
    (net (code "56") (name "Net-(D1-A)") (class "Default")
      (node (ref "D1") (pin "2") (pinfunction "A_2") (pintype "passive"))
      (node (ref "D2") (pin "1") (pinfunction "K_1") (pintype "passive"))
      (node (ref "J2") (pin "4") (pinfunction "SN_4") (pintype "input"))
      (node (ref "R14") (pin "1") (pinfunction "1_1") (pintype "passive"))
      (node (ref "R17") (pin "1") (pinfunction "1_1") (pintype "passive"))
    )
    (net (code "57") (name "Net-(D6-K)") (class "Default")
      (node (ref "D6") (pin "1") (pinfunction "K_1") (pintype "passive"))
      (node (ref "J2") (pin "3") (pinfunction "R_3") (pintype "input"))
      (node (ref "R16") (pin "1") (pinfunction "1_1") (pintype "passive"))
      (node (ref "R18") (pin "1") (pinfunction "1_1") (pintype "passive"))
    )
    (net (code "58") (name "Net-(D7-A)") (class "Default")
      (node (ref "D7") (pin "2") (pinfunction "A_2") (pintype "passive"))
      (node (ref "D8") (pin "1") (pinfunction "K_1") (pintype "passive"))
      (node (ref "ZS1") (pin "2") (pinfunction "2_2") (pintype "passive"))
    )
    (net (code "59") (name "Net-(D7-K)") (class "Default")
      (node (ref "C15") (pin "2") (pinfunction "2_2") (pintype "passive"))
      (node (ref "C21") (pin "2") (pinfunction "2_2") (pintype "passive"))
      (node (ref "C33") (pin "1") (pinfunction "1_1") (pintype "passive"))
      (node (ref "D7") (pin "1") (pinfunction "K_1") (pintype "passive"))
      (node (ref "D9") (pin "1") (pinfunction "K_1") (pintype "passive"))
      (node (ref "U3") (pin "1") (pinfunction "IN_1") (pintype "power_in"))
      (node (ref "U4") (pin "1") (pinfunction "IN_1") (pintype "power_in"))
    )
    (net (code "60") (name "Net-(D10-K)") (class "Default")
      (node (ref "D10") (pin "1") (pinfunction "K_1") (pintype "passive"))
      (node (ref "D9") (pin "2") (pinfunction "A_2") (pintype "passive"))
      (node (ref "ZS1") (pin "1") (pinfunction "1_1") (pintype "passive"))
    )
    (net (code "61") (name "Net-(J1-Pad6)") (class "Default")
      (node (ref "J1") (pin "6") (pinfunction "6_6") (pintype "passive"))
      (node (ref "J1") (pin "7") (pinfunction "7_7") (pintype "passive"))
      (node (ref "J1") (pin "8") (pinfunction "8_8") (pintype "passive"))
      (node (ref "J1") (pin "9") (pinfunction "9_9") (pintype "passive"))
    )
    (net (code "62") (name "Net-(R6-Pad1)") (class "Default")
      (node (ref "R6") (pin "1") (pinfunction "1_1") (pintype "passive"))
      (node (ref "X1") (pin "1") (pinfunction "HOT_1") (pintype "passive"))
    )
    (net (code "63") (name "Net-(R7-Pad2)") (class "Default")
      (node (ref "R7") (pin "2") (pinfunction "2_2") (pintype "passive"))
      (node (ref "X2") (pin "1") (pinfunction "HOT_1") (pintype "passive"))
    )
    (net (code "64") (name "Net-(U1-VDDCORE{slash}VCAP)") (class "Default")
      (node (ref "C29") (pin "1") (pinfunction "1_1") (pintype "passive"))
      (node (ref "C8") (pin "2") (pinfunction "2_2") (pintype "passive"))
      (node (ref "U1") (pin "10") (pinfunction "VDDCORE/VCAP_10") (pintype "power_in"))
    )
    (net (code "65") (name "Net-(U2-!XRESET)") (class "Default")
      (node (ref "R13") (pin "2") (pinfunction "2_2") (pintype "passive"))
      (node (ref "U2") (pin "3") (pinfunction "!XRESET_3") (pintype "passive"))
    )
    (net (code "66") (name "Net-(U2-AVDD0)") (class "Default")
      (node (ref "C22") (pin "2") (pinfunction "2_2") (pintype "passive"))
      (node (ref "C7") (pin "2") (pinfunction "2_2") (pintype "passive"))
      (node (ref "U2") (pin "38") (pinfunction "AVDD0_38") (pintype "passive"))
      (node (ref "U2") (pin "43") (pinfunction "AVDD1_43") (pintype "passive"))
      (node (ref "U2") (pin "45") (pinfunction "AVDD2_45") (pintype "passive"))
    )
    (net (code "67") (name "Net-(U5-VCC)") (class "Default")
      (node (ref "C10") (pin "2") (pinfunction "2_2") (pintype "passive"))
      (node (ref "U5") (pin "8") (pinfunction "VCC_8") (pintype "power_in"))
    )
    (net (code "68") (name "Net-(U6-VCC)") (class "Default")
      (node (ref "C16") (pin "2") (pinfunction "2_2") (pintype "passive"))
      (node (ref "U6") (pin "8") (pinfunction "VCC_8") (pintype "power_in"))
    )
    (net (code "69") (name "unconnected-(C32-RCT-Pad6)") (class "Default")
      (node (ref "C32") (pin "6") (pinfunction "RCT_6") (pintype "passive"))
    )
    (net (code "70") (name "unconnected-(D5-A-Pad2)") (class "Default")
      (node (ref "D5") (pin "2") (pinfunction "A_2") (pintype "passive"))
    )
    (net (code "71") (name "unconnected-(J2-NC-Pad10)") (class "Default")
      (node (ref "J2") (pin "10") (pinfunction "NC_10") (pintype "passive"))
    )
    (net (code "72") (name "unconnected-(J2-S-Pad1)") (class "Default")
      (node (ref "J2") (pin "1") (pinfunction "S_1") (pintype "power_in"))
    )
    (net (code "73") (name "unconnected-(J3-Pad7)") (class "Default")
      (node (ref "J3") (pin "7") (pinfunction "7_7") (pintype "passive"))
    )
    (net (code "74") (name "unconnected-(J3-Pad8)") (class "Default")
      (node (ref "J3") (pin "8") (pinfunction "8_8") (pintype "passive"))
    )
    (net (code "75") (name "unconnected-(J4-Pad4)") (class "Default")
      (node (ref "J4") (pin "4") (pinfunction "4_4") (pintype "passive"))
    )
    (net (code "76") (name "unconnected-(J4-Pad5)") (class "Default")
      (node (ref "J4") (pin "5") (pinfunction "5_5") (pintype "passive"))
    )
    (net (code "77") (name "unconnected-(J4-Pad6)") (class "Default")
      (node (ref "J4") (pin "6") (pinfunction "6_6") (pintype "passive"))
    )
    (net (code "78") (name "unconnected-(J4-Pad8)") (class "Default")
      (node (ref "J4") (pin "8") (pinfunction "8_8") (pintype "passive"))
    )
    (net (code "79") (name "unconnected-(U1-ENVREG-Pad18)") (class "Default")
      (node (ref "U1") (pin "18") (pinfunction "ENVREG_18") (pintype "input+no_connect"))
    )
    (net (code "80") (name "unconnected-(U1-OSC2{slash}CLKO-Pad40)") (class "Default")
      (node (ref "U1") (pin "40") (pinfunction "OSC2/CLKO_40") (pintype "output"))
    )
    (net (code "81") (name "unconnected-(U1-RA2{slash}AN2{slash}VREF--Pad22)") (class "Default")
      (node (ref "U1") (pin "22") (pinfunction "RA2/AN2/VREF-_22") (pintype "bidirectional"))
    )
    (net (code "82") (name "unconnected-(U1-RA3{slash}AN3{slash}VREF+-Pad21)") (class "Default")
      (node (ref "U1") (pin "21") (pinfunction "RA3/AN3/VREF+_21") (pintype "bidirectional"))
    )
    (net (code "83") (name "unconnected-(U1-RA4{slash}T0CKI-Pad28)") (class "Default")
      (node (ref "U1") (pin "28") (pinfunction "RA4/T0CKI_28") (pintype "bidirectional"))
    )
    (net (code "84") (name "unconnected-(U1-RA5{slash}AN4-Pad27)") (class "Default")
      (node (ref "U1") (pin "27") (pinfunction "RA5/AN4_27") (pintype "bidirectional"))
    )
    (net (code "85") (name "unconnected-(U1-RB3{slash}INT3-Pad6)") (class "Default")
      (node (ref "U1") (pin "6") (pinfunction "RB3/INT3_6") (pintype "bidirectional"))
    )
    (net (code "86") (name "unconnected-(U1-RB4{slash}KBI0-Pad44)") (class "Default")
      (node (ref "U1") (pin "44") (pinfunction "RB4/KBI0_44") (pintype "bidirectional"))
    )
    (net (code "87") (name "unconnected-(U1-RB5{slash}KBI1-Pad43)") (class "Default")
      (node (ref "U1") (pin "43") (pinfunction "RB5/KBI1_43") (pintype "bidirectional"))
    )
    (net (code "88") (name "unconnected-(U1-RC0{slash}T1OSO{slash}T13CKI-Pad30)") (class "Default")
      (node (ref "U1") (pin "30") (pinfunction "RC0/T1OSO/T13CKI_30") (pintype "bidirectional"))
    )
    (net (code "89") (name "unconnected-(U1-RC1{slash}T1OSI{slash}ECCP2{slash}P2A-Pad29)") (class "Default")
      (node (ref "U1") (pin "29") (pinfunction "RC1/T1OSI/ECCP2/P2A_29") (pintype "bidirectional"))
    )
    (net (code "90") (name "unconnected-(U1-RC2{slash}ECCP1{slash}P1A-Pad33)") (class "Default")
      (node (ref "U1") (pin "33") (pinfunction "RC2/ECCP1/P1A_33") (pintype "bidirectional"))
    )
    (net (code "91") (name "unconnected-(U1-RC6{slash}TX1{slash}CK1-Pad31)") (class "Default")
      (node (ref "U1") (pin "31") (pinfunction "RC6/TX1/CK1_31") (pintype "bidirectional"))
    )
    (net (code "92") (name "unconnected-(U1-RC7{slash}RX1{slash}DT1-Pad32)") (class "Default")
      (node (ref "U1") (pin "32") (pinfunction "RC7/RX1/DT1_32") (pintype "bidirectional"))
    )
    (net (code "93") (name "unconnected-(U1-RD0{slash}P1B-Pad60)") (class "Default")
      (node (ref "U1") (pin "60") (pinfunction "RD0/P1B_60") (pintype "bidirectional"))
    )
    (net (code "94") (name "unconnected-(U1-RD1{slash}ECCP3{slash}P3A-Pad59)") (class "Default")
      (node (ref "U1") (pin "59") (pinfunction "RD1/ECCP3/P3A_59") (pintype "bidirectional"))
    )
    (net (code "95") (name "unconnected-(U1-RD2{slash}CCP4{slash}P3D-Pad58)") (class "Default")
      (node (ref "U1") (pin "58") (pinfunction "RD2/CCP4/P3D_58") (pintype "bidirectional"))
    )
    (net (code "96") (name "unconnected-(U1-RG4{slash}CCP5{slash}P1D-Pad8)") (class "Default")
      (node (ref "U1") (pin "8") (pinfunction "RG4/CCP5/P1D_8") (pintype "bidirectional"))
    )
    (net (code "97") (name "unconnected-(U2-NC-Pad1)") (class "Default")
      (node (ref "U2") (pin "1") (pinfunction "NC_1") (pintype "passive"))
    )
    (net (code "98") (name "unconnected-(U2-NC-Pad2)") (class "Default")
      (node (ref "U2") (pin "2") (pinfunction "NC_2") (pintype "passive"))
    )
    (net (code "99") (name "unconnected-(U2-NC-Pad5)") (class "Default")
      (node (ref "U2") (pin "5") (pinfunction "NC_5") (pintype "passive"))
    )
    (net (code "100") (name "unconnected-(U2-NC-Pad7)") (class "Default")
      (node (ref "U2") (pin "7") (pinfunction "NC_7") (pintype "passive"))
    )
    (net (code "101") (name "unconnected-(U2-NC-Pad11)") (class "Default")
      (node (ref "U2") (pin "11") (pinfunction "NC_11") (pintype "passive"))
    )
    (net (code "102") (name "unconnected-(U2-NC-Pad12)") (class "Default")
      (node (ref "U2") (pin "12") (pinfunction "NC_12") (pintype "passive"))
    )
    (net (code "103") (name "unconnected-(U2-NC-Pad15)") (class "Default")
      (node (ref "U2") (pin "15") (pinfunction "NC_15") (pintype "passive"))
    )
    (net (code "104") (name "unconnected-(U2-NC-Pad24)") (class "Default")
      (node (ref "U2") (pin "24") (pinfunction "NC_24") (pintype "passive"))
    )
    (net (code "105") (name "unconnected-(U2-NC-Pad25)") (class "Default")
      (node (ref "U2") (pin "25") (pinfunction "NC_25") (pintype "passive"))
    )
    (net (code "106") (name "unconnected-(U2-NC-Pad27)") (class "Default")
      (node (ref "U2") (pin "27") (pinfunction "NC_27") (pintype "passive"))
    )
    (net (code "107") (name "unconnected-(U2-NC-Pad31)") (class "Default")
      (node (ref "U2") (pin "31") (pinfunction "NC_31") (pintype "passive"))
    )
    (net (code "108") (name "unconnected-(U2-NC-Pad35)") (class "Default")
      (node (ref "U2") (pin "35") (pinfunction "NC_35") (pintype "passive"))
    )
    (net (code "109") (name "unconnected-(U2-NC-Pad36)") (class "Default")
      (node (ref "U2") (pin "36") (pinfunction "NC_36") (pintype "passive"))
    )
    (net (code "110") (name "unconnected-(U2-NC-Pad48)") (class "Default")
      (node (ref "U2") (pin "48") (pinfunction "NC_48") (pintype "passive"))
    )
    (net (code "111") (name "unconnected-(U2-XTALO-Pad17)") (class "Default")
      (node (ref "U2") (pin "17") (pinfunction "XTALO_17") (pintype "passive"))
    )
    (net (code "112") (name "unconnected-(U5-NC-Pad3)") (class "Default")
      (node (ref "U5") (pin "3") (pinfunction "NC_3") (pintype "passive"))
    )
    (net (code "113") (name "unconnected-(U6-NC-Pad3)") (class "Default")
      (node (ref "U6") (pin "3") (pinfunction "NC_3") (pintype "passive"))
    )
  )
)
